# CurrentMonitor.net
KiCad netlist of a schematic drawn in EAGLE
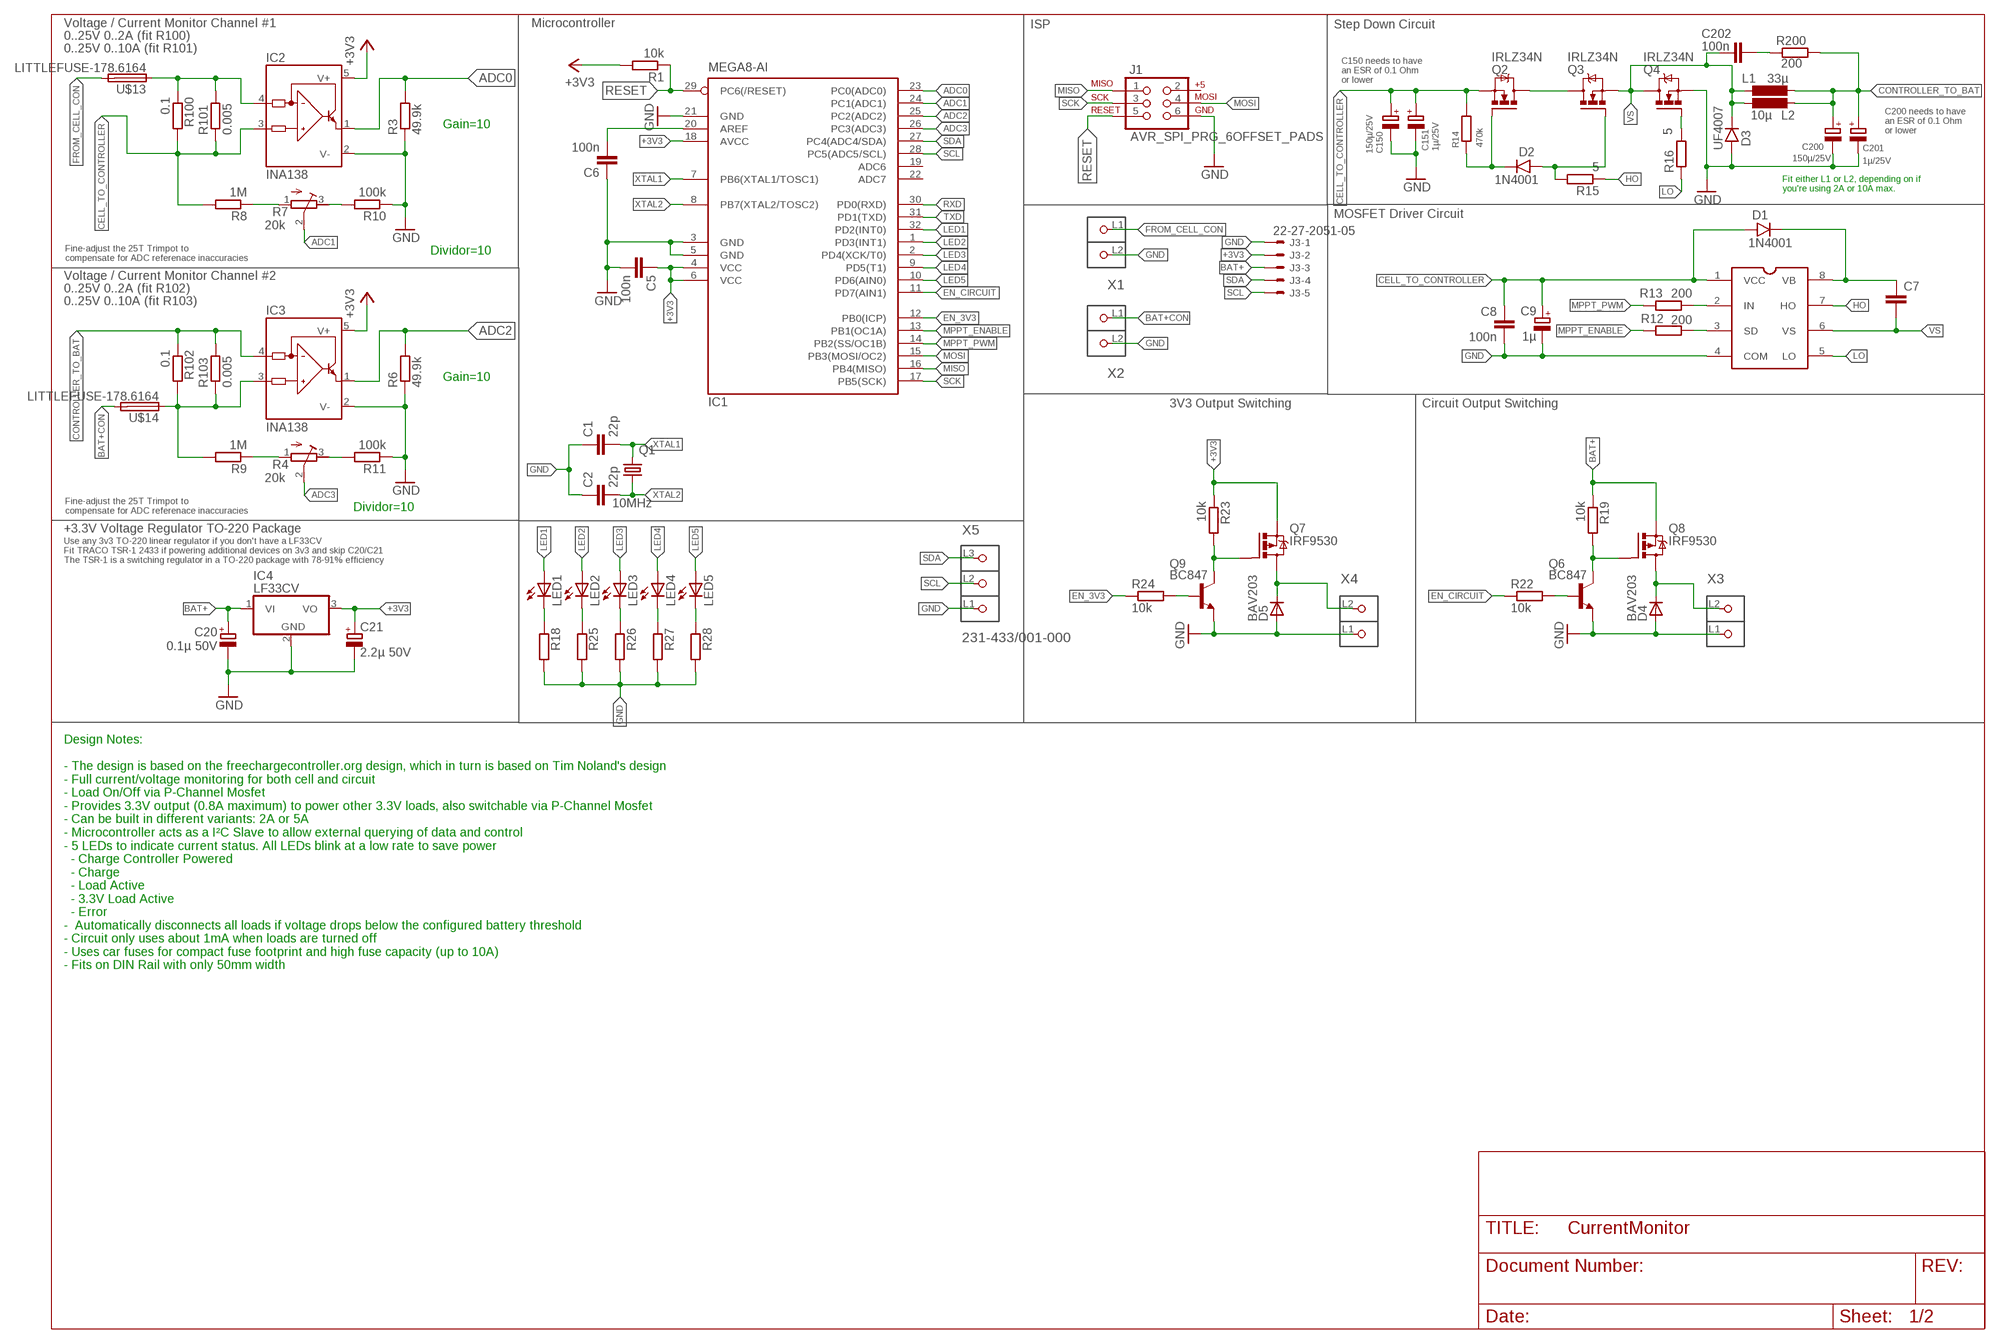
[diagram p0: schematic, sheet 1]
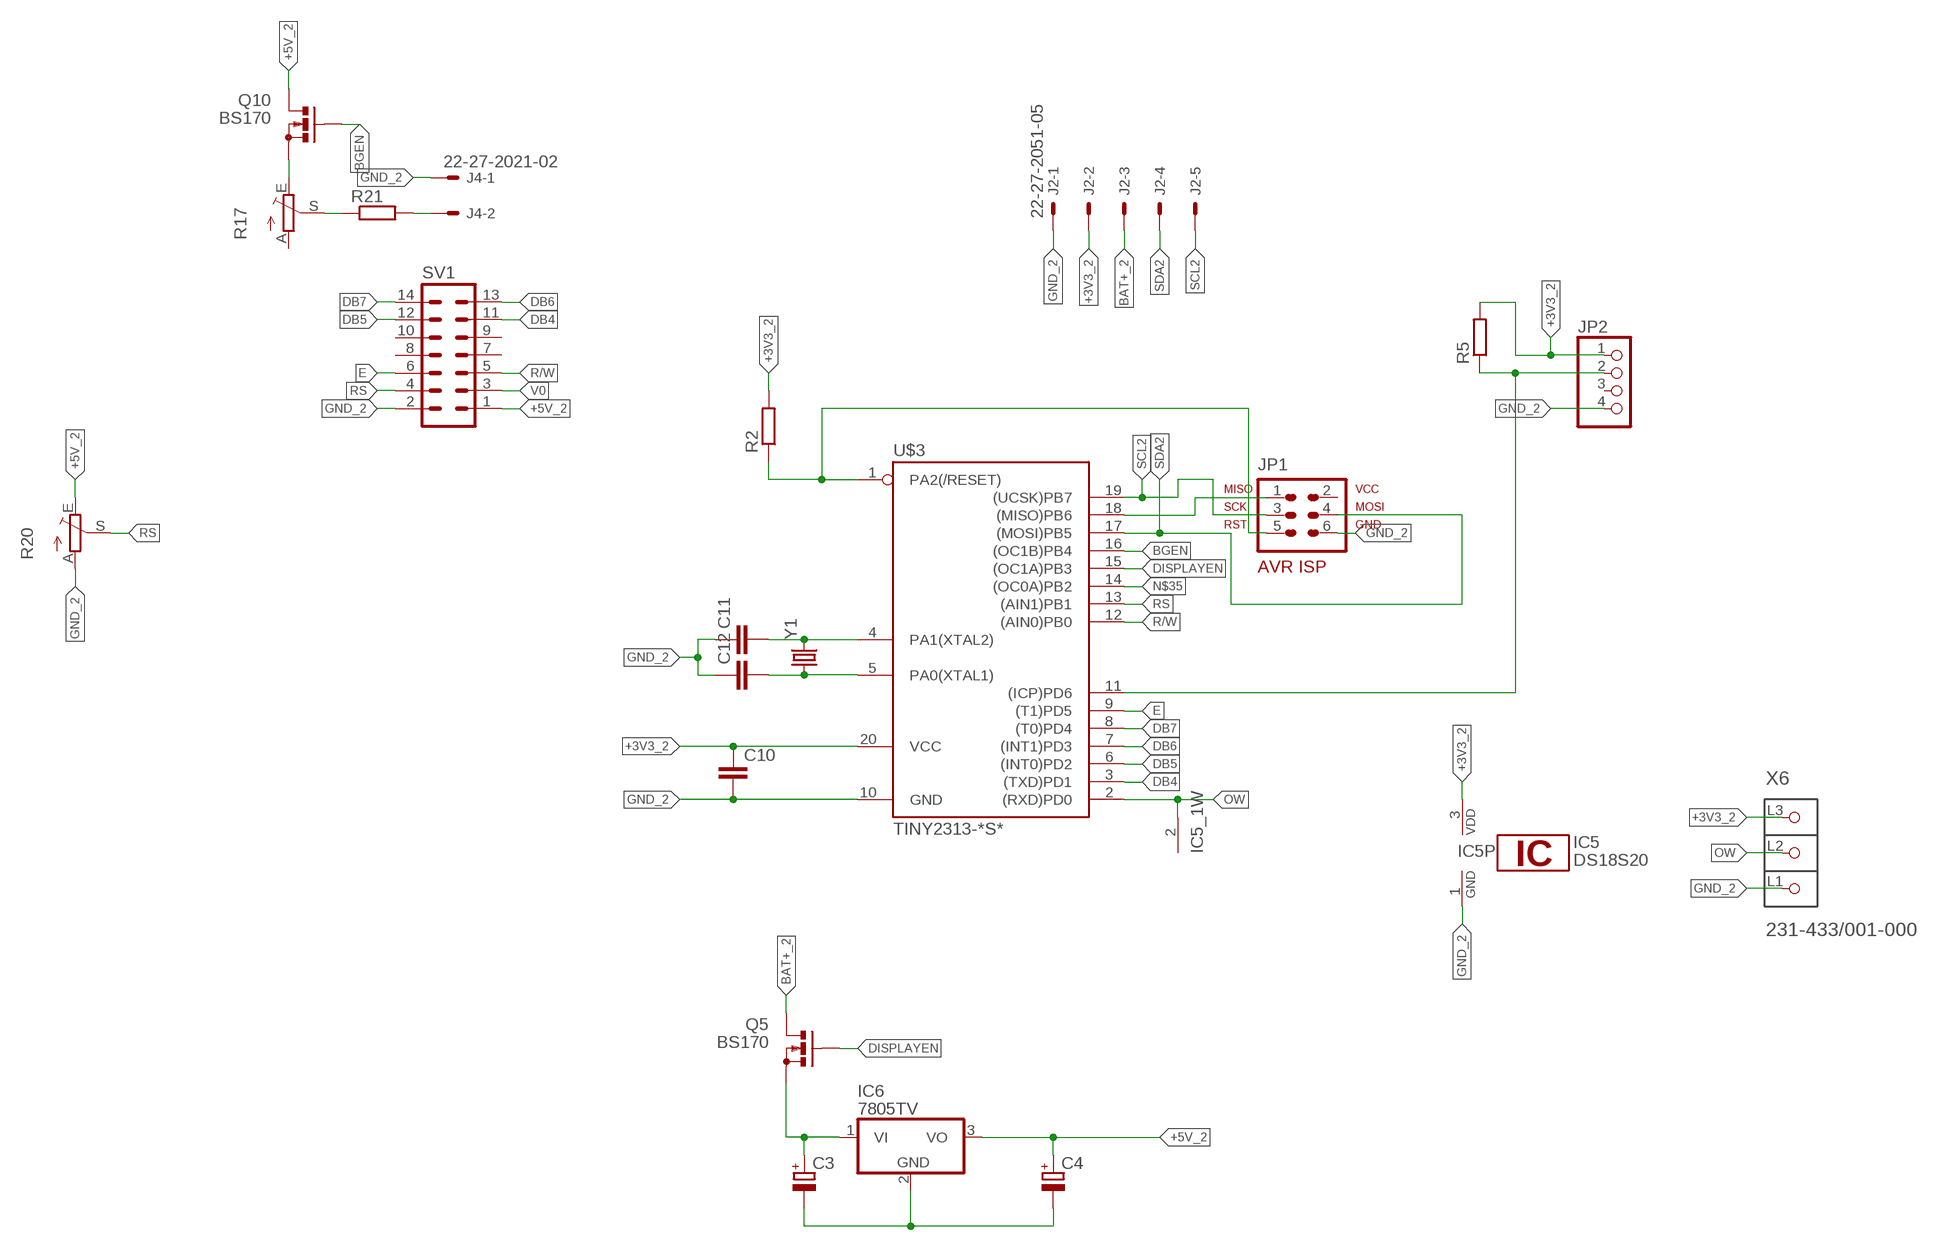
[diagram p1: schematic, sheet 2]

(export (version "E")
  (design (tool "Eeschema 10.0.6"))
  (components
    (comp (ref "C3")
      (value "CPOL-EUE3.5-8")
      (footprint "eagle-import:E3,5-8")
      (libsource (lib "eagle-import") (part "CPOL-EUE3.5-8"))
    )
    (comp (ref "C4")
      (value "CPOL-EUE3.5-8")
      (footprint "eagle-import:E3,5-8")
      (libsource (lib "eagle-import") (part "CPOL-EUE3.5-8"))
    )
    (comp (ref "C10")
      (value "C-EUC0805")
      (footprint "eagle-import:C0805")
      (libsource (lib "eagle-import") (part "C-EUC0805"))
    )
    (comp (ref "C11")
      (value "C-EUC0805")
      (footprint "eagle-import:C0805")
      (libsource (lib "eagle-import") (part "resistor_C-EUC0805"))
    )
    (comp (ref "C12")
      (value "C-EUC0805")
      (footprint "eagle-import:C0805")
      (libsource (lib "eagle-import") (part "resistor_C-EUC0805"))
    )
    (comp (ref "IC5")
      (value "DS18S20")
      (footprint "eagle-import:TO92-")
      (libsource (lib "eagle-import") (part "DS18S20"))
    )
    (comp (ref "IC6")
      (value "7805TV")
      (footprint "eagle-import:TO220V")
      (libsource (lib "eagle-import") (part "78TV05"))
    )
    (comp (ref "J2")
      (value "22-27-2051-05")
      (footprint "eagle-import:6410-05")
      (libsource (lib "eagle-import") (part "22-?-0527-2051"))
    )
    (comp (ref "J4")
      (value "22-27-2021-02")
      (footprint "eagle-import:6410-02")
      (libsource (lib "eagle-import") (part "22-?-0227-2021"))
    )
    (comp (ref "JP1")
      (value "AVR-ISP-6VERT")
      (footprint "eagle-import:AVR-ISP-6")
      (libsource (lib "eagle-import") (part "AVR-ISP-6VERT"))
    )
    (comp (ref "JP2")
      (value "PINHD-1X4")
      (footprint "eagle-import:1X04")
      (libsource (lib "eagle-import") (part "PINHD-1X4"))
    )
    (comp (ref "Q5")
      (value "BS170")
      (footprint "eagle-import:SOT54E")
      (libsource (lib "eagle-import") (part "BS170"))
    )
    (comp (ref "Q10")
      (value "BS170")
      (footprint "eagle-import:SOT54E")
      (libsource (lib "eagle-import") (part "BS170"))
    )
    (comp (ref "R2")
      (value "R-EU_R0805")
      (footprint "eagle-import:R0805")
      (libsource (lib "eagle-import") (part "R-EU_R0805"))
    )
    (comp (ref "R5")
      (value "R-EU_R0805")
      (footprint "eagle-import:R0805")
      (libsource (lib "eagle-import") (part "resistor_R-EU_R0805"))
    )
    (comp (ref "R17")
      (value "TRIM_EU-PT10")
      (footprint "eagle-import:PT-10")
      (libsource (lib "eagle-import") (part "TRIM_EU-PT10"))
    )
    (comp (ref "R20")
      (value "TRIM_EU-PT10")
      (footprint "eagle-import:PT-10")
      (libsource (lib "eagle-import") (part "TRIM_EU-PT10"))
    )
    (comp (ref "R21")
      (value "R-EU_R0805")
      (footprint "eagle-import:R0805")
      (libsource (lib "eagle-import") (part "R-EU_R0805"))
    )
    (comp (ref "SV1")
      (value "ML14")
      (footprint "eagle-import:ML14")
      (libsource (lib "eagle-import") (part "ML14"))
    )
    (comp (ref "U$3")
      (value "TINY2313-*S*")
      (footprint "eagle-import:SO20L$")
      (libsource (lib "eagle-import") (part "TINY2313-S"))
    )
    (comp (ref "X6")
      (value "231-433/001-000")
      (footprint "eagle-import:P-231-433_001-000")
      (libsource (lib "eagle-import") (part "231-433/001-000"))
    )
    (comp (ref "Y1")
      (value "CRYSTALHC49US")
      (footprint "eagle-import:HC49US")
      (libsource (lib "eagle-import") (part "CRYSTALHC49US"))
    )
    (comp (ref "C1")
      (value "22p")
      (footprint "eagle-import:C1206")
      (libsource (lib "eagle-import") (part "C-EUC1206"))
    )
    (comp (ref "C2")
      (value "22p")
      (footprint "eagle-import:C1206")
      (libsource (lib "eagle-import") (part "C-EUC1206"))
    )
    (comp (ref "C5")
      (value "100n")
      (footprint "eagle-import:C0805")
      (libsource (lib "eagle-import") (part "resistor_C-EUC0805"))
    )
    (comp (ref "C6")
      (value "100n")
      (footprint "eagle-import:C0805")
      (libsource (lib "eagle-import") (part "resistor_C-EUC0805"))
    )
    (comp (ref "C7")
      (value "C-EUC0805")
      (footprint "eagle-import:C0805")
      (libsource (lib "eagle-import") (part "resistor_C-EUC0805"))
    )
    (comp (ref "C8")
      (value "100n")
      (footprint "eagle-import:C0805")
      (libsource (lib "eagle-import") (part "resistor_C-EUC0805"))
    )
    (comp (ref "C9")
      (value "1µ")
      (footprint "eagle-import:PANASONIC_A")
      (libsource (lib "eagle-import") (part "CPOL-EUA"))
    )
    (comp (ref "C20")
      (value "0.1µ 50V")
      (footprint "eagle-import:PANASONIC_A")
      (libsource (lib "eagle-import") (part "CPOL-EUA"))
    )
    (comp (ref "C21")
      (value "2.2µ 50V")
      (footprint "eagle-import:PANASONIC_B")
      (libsource (lib "eagle-import") (part "CPOL-EUB"))
    )
    (comp (ref "C150")
      (value "150µ/25V")
      (footprint "eagle-import:PANASONIC_F")
      (libsource (lib "eagle-import") (part "CPOL-EUF"))
    )
    (comp (ref "C151")
      (value "1µ/25V")
      (footprint "eagle-import:PANASONIC_B")
      (libsource (lib "eagle-import") (part "CPOL-EUB"))
    )
    (comp (ref "C200")
      (value "150µ/25V")
      (footprint "eagle-import:PANASONIC_F")
      (libsource (lib "eagle-import") (part "CPOL-EUF"))
    )
    (comp (ref "C201")
      (value "1µ/25V")
      (footprint "eagle-import:PANASONIC_B")
      (libsource (lib "eagle-import") (part "CPOL-EUB"))
    )
    (comp (ref "C202")
      (value "100n")
      (footprint "eagle-import:C0805")
      (libsource (lib "eagle-import") (part "resistor_C-EUC0805"))
    )
    (comp (ref "D1")
      (value "1N4001")
      (footprint "eagle-import:DO41-3")
      (libsource (lib "eagle-import") (part "DO41.3"))
    )
    (comp (ref "D2")
      (value "1N4001")
      (footprint "eagle-import:DO41-3")
      (libsource (lib "eagle-import") (part "DO41.3"))
    )
    (comp (ref "D3")
      (value "UF4007")
      (footprint "eagle-import:DO41-3")
      (libsource (lib "eagle-import") (part "DO41.3"))
    )
    (comp (ref "D4")
      (value "BAV203")
      (footprint "eagle-import:SOD80")
      (libsource (lib "eagle-import") (part "D-SOD-80"))
    )
    (comp (ref "D5")
      (value "BAV203")
      (footprint "eagle-import:SOD80")
      (libsource (lib "eagle-import") (part "D-SOD-80"))
    )
    (comp (ref "IC1")
      (value "MEGA8-AI")
      (footprint "eagle-import:TQFP32-08")
      (fields (field (name "MPN") "ATMEGA8-16AU"))
      (libsource (lib "eagle-import") (part "MEGA8-AI"))
    )
    (comp (ref "IC2")
      (value "INA138")
      (footprint "eagle-import:SOT23-5")
      (fields (field (name "MF") "TEXAS INSTRUMENTS") (field (name "MPN") "INA138NA/250"))
      (libsource (lib "eagle-import") (part "INA138"))
    )
    (comp (ref "IC3")
      (value "INA138")
      (footprint "eagle-import:SOT23-5")
      (fields (field (name "MF") "TEXAS INSTRUMENTS") (field (name "MPN") "INA138NA/250"))
      (libsource (lib "eagle-import") (part "INA138"))
    )
    (comp (ref "IC4")
      (value "LF33CV")
      (footprint "eagle-import:TO220V")
      (libsource (lib "eagle-import") (part "78TV05"))
    )
    (comp (ref "J1")
      (value "AVR_SPI_PRG_6OFFSET_PADS")
      (footprint "eagle-import:2X3_OFFSET")
      (libsource (lib "eagle-import") (part "AVR_SPI_PRG_6OFFSET_PADS"))
    )
    (comp (ref "J3")
      (value "22-27-2051-05")
      (footprint "eagle-import:6410-05")
      (libsource (lib "eagle-import") (part "22-?-0527-2051"))
    )
    (comp (ref "L1")
      (value "33µ")
      (footprint "eagle-import:PISM")
      (libsource (lib "eagle-import") (part "L-EUPISM"))
    )
    (comp (ref "L2")
      (value "10µ")
      (footprint "eagle-import:PISR")
      (libsource (lib "eagle-import") (part "L-EUPISR"))
    )
    (comp (ref "LED1")
      (value "LEDCHIPLED_1206")
      (footprint "eagle-import:CHIPLED_1206")
      (libsource (lib "eagle-import") (part "LEDCHIPLED_1206"))
    )
    (comp (ref "LED2")
      (value "LEDCHIPLED_1206")
      (footprint "eagle-import:CHIPLED_1206")
      (libsource (lib "eagle-import") (part "LEDCHIPLED_1206"))
    )
    (comp (ref "LED3")
      (value "LEDCHIPLED_1206")
      (footprint "eagle-import:CHIPLED_1206")
      (libsource (lib "eagle-import") (part "LEDCHIPLED_1206"))
    )
    (comp (ref "LED4")
      (value "LEDCHIPLED_1206")
      (footprint "eagle-import:CHIPLED_1206")
      (libsource (lib "eagle-import") (part "LEDCHIPLED_1206"))
    )
    (comp (ref "LED5")
      (value "LEDCHIPLED_1206")
      (footprint "eagle-import:CHIPLED_1206")
      (libsource (lib "eagle-import") (part "LEDCHIPLED_1206"))
    )
    (comp (ref "Q1")
      (value "10MHz")
      (footprint "eagle-import:CTS406")
      (libsource (lib "eagle-import") (part "CRYSTALCTS406"))
    )
    (comp (ref "Q2")
      (value "IRLZ34N")
      (footprint "eagle-import:TO220BV")
      (libsource (lib "eagle-import") (part "IRF520"))
    )
    (comp (ref "Q3")
      (value "IRLZ34N")
      (footprint "eagle-import:TO220BV")
      (libsource (lib "eagle-import") (part "IRF520"))
    )
    (comp (ref "Q4")
      (value "IRLZ34N")
      (footprint "eagle-import:TO220BV")
      (libsource (lib "eagle-import") (part "IRF520"))
    )
    (comp (ref "Q6")
      (value "BC847")
      (footprint "eagle-import:SOT23")
      (libsource (lib "eagle-import") (part "BC847SMDALT1"))
    )
    (comp (ref "Q7")
      (value "IRF9530")
      (footprint "eagle-import:TO220BV")
      (libsource (lib "eagle-import") (part "IRF9530"))
    )
    (comp (ref "Q8")
      (value "IRF9530")
      (footprint "eagle-import:TO220BV")
      (libsource (lib "eagle-import") (part "IRF9530"))
    )
    (comp (ref "Q9")
      (value "BC847")
      (footprint "eagle-import:SOT23")
      (libsource (lib "eagle-import") (part "BC847SMDALT1"))
    )
    (comp (ref "R1")
      (value "10k")
      (footprint "eagle-import:R0805")
      (libsource (lib "eagle-import") (part "R-EU_R0805"))
    )
    (comp (ref "R3")
      (value "49.9k")
      (footprint "eagle-import:R0805")
      (libsource (lib "eagle-import") (part "R-EU_R0805"))
    )
    (comp (ref "R4")
      (value "20k")
      (footprint "eagle-import:RTRIM64W")
      (libsource (lib "eagle-import") (part "R-TRIMM64W"))
    )
    (comp (ref "R6")
      (value "49.9k")
      (footprint "eagle-import:R0805")
      (libsource (lib "eagle-import") (part "R-EU_R0805"))
    )
    (comp (ref "R7")
      (value "20k")
      (footprint "eagle-import:RTRIM64W")
      (libsource (lib "eagle-import") (part "R-TRIMM64W"))
    )
    (comp (ref "R8")
      (value "1M")
      (footprint "eagle-import:R0805")
      (libsource (lib "eagle-import") (part "R-EU_R0805"))
    )
    (comp (ref "R9")
      (value "1M")
      (footprint "eagle-import:R0805")
      (libsource (lib "eagle-import") (part "R-EU_R0805"))
    )
    (comp (ref "R10")
      (value "100k")
      (footprint "eagle-import:R0805")
      (libsource (lib "eagle-import") (part "R-EU_R0805"))
    )
    (comp (ref "R11")
      (value "100k")
      (footprint "eagle-import:R0805")
      (libsource (lib "eagle-import") (part "R-EU_R0805"))
    )
    (comp (ref "R12")
      (value "200")
      (footprint "eagle-import:R0805")
      (libsource (lib "eagle-import") (part "R-EU_R0805"))
    )
    (comp (ref "R13")
      (value "200")
      (footprint "eagle-import:R0805")
      (libsource (lib "eagle-import") (part "R-EU_R0805"))
    )
    (comp (ref "R14")
      (value "470k")
      (footprint "eagle-import:R0805")
      (libsource (lib "eagle-import") (part "R-EU_R0805"))
    )
    (comp (ref "R15")
      (value "5")
      (footprint "eagle-import:R0805")
      (libsource (lib "eagle-import") (part "resistor_R-EU_R0805"))
    )
    (comp (ref "R16")
      (value "5")
      (footprint "eagle-import:R0805")
      (libsource (lib "eagle-import") (part "resistor_R-EU_R0805"))
    )
    (comp (ref "R18")
      (value "R-EU_R0805")
      (footprint "eagle-import:R0805")
      (libsource (lib "eagle-import") (part "R-EU_R0805"))
    )
    (comp (ref "R19")
      (value "10k")
      (footprint "eagle-import:R0805")
      (libsource (lib "eagle-import") (part "R-EU_R0805"))
    )
    (comp (ref "R22")
      (value "10k")
      (footprint "eagle-import:R0805")
      (libsource (lib "eagle-import") (part "resistor_R-EU_R0805"))
    )
    (comp (ref "R23")
      (value "10k")
      (footprint "eagle-import:R0805")
      (libsource (lib "eagle-import") (part "R-EU_R0805"))
    )
    (comp (ref "R24")
      (value "10k")
      (footprint "eagle-import:R0805")
      (libsource (lib "eagle-import") (part "resistor_R-EU_R0805"))
    )
    (comp (ref "R25")
      (value "R-EU_R0805")
      (footprint "eagle-import:R0805")
      (libsource (lib "eagle-import") (part "R-EU_R0805"))
    )
    (comp (ref "R26")
      (value "R-EU_R0805")
      (footprint "eagle-import:R0805")
      (libsource (lib "eagle-import") (part "R-EU_R0805"))
    )
    (comp (ref "R27")
      (value "R-EU_R0805")
      (footprint "eagle-import:R0805")
      (libsource (lib "eagle-import") (part "R-EU_R0805"))
    )
    (comp (ref "R28")
      (value "R-EU_R0805")
      (footprint "eagle-import:R0805")
      (libsource (lib "eagle-import") (part "R-EU_R0805"))
    )
    (comp (ref "R100")
      (value "0.1")
      (footprint "eagle-import:R1206")
      (libsource (lib "eagle-import") (part "resistor_R-EU_R1206"))
    )
    (comp (ref "R101")
      (value "0.005")
      (footprint "eagle-import:R2512")
      (libsource (lib "eagle-import") (part "resistor_R-EU_R2512"))
    )
    (comp (ref "R102")
      (value "0.1")
      (footprint "eagle-import:R1206")
      (libsource (lib "eagle-import") (part "resistor_R-EU_R1206"))
    )
    (comp (ref "R103")
      (value "0.005")
      (footprint "eagle-import:R2512")
      (libsource (lib "eagle-import") (part "resistor_R-EU_R2512"))
    )
    (comp (ref "R200")
      (value "200")
      (footprint "eagle-import:R0805")
      (libsource (lib "eagle-import") (part "R-EU_R0805"))
    )
    (comp (ref "U$1")
      (value "IR2104S")
      (footprint "eagle-import:IR2104S")
      (libsource (lib "eagle-import") (part "IR2104S"))
    )
    (comp (ref "U$13")
      (value "LITTLEFUSE-178.6164")
      (footprint "eagle-import:LITTLEFUSE-178-6164")
      (libsource (lib "eagle-import") (part "LITTLEFUSE-178.6164"))
    )
    (comp (ref "U$14")
      (value "LITTLEFUSE-178.6164")
      (footprint "eagle-import:LITTLEFUSE-178-6164")
      (libsource (lib "eagle-import") (part "LITTLEFUSE-178.6164"))
    )
    (comp (ref "X1")
      (value "231-432/001-000")
      (footprint "eagle-import:P-231-432_001-000")
      (libsource (lib "eagle-import") (part "231-432/001-000"))
    )
    (comp (ref "X2")
      (value "231-432/001-000")
      (footprint "eagle-import:P-231-432_001-000")
      (libsource (lib "eagle-import") (part "231-432/001-000"))
    )
    (comp (ref "X3")
      (value "231-432/001-000")
      (footprint "eagle-import:P-231-432_001-000")
      (libsource (lib "eagle-import") (part "231-432/001-000"))
    )
    (comp (ref "X4")
      (value "231-432/001-000")
      (footprint "eagle-import:P-231-432_001-000")
      (libsource (lib "eagle-import") (part "231-432/001-000"))
    )
    (comp (ref "X5")
      (value "231-433/001-000")
      (footprint "eagle-import:P-231-433_001-000")
      (libsource (lib "eagle-import") (part "231-433/001-000"))
    )
  )
  (nets
    (net (code "1") (name "+3V3") (class "Default")
      (node (ref "C21") (pin "+") (pinfunction "+_+") (pintype "passive"))
      (node (ref "C5") (pin "1") (pinfunction "1_1") (pintype "passive"))
      (node (ref "IC1") (pin "18") (pinfunction "AVCC_18") (pintype "power_in"))
      (node (ref "IC1") (pin "4") (pinfunction "VCC_4") (pintype "power_in"))
      (node (ref "IC1") (pin "6") (pinfunction "VCC_6") (pintype "power_in"))
      (node (ref "IC2") (pin "5") (pinfunction "V+_5") (pintype "power_in"))
      (node (ref "IC3") (pin "5") (pinfunction "V+_5") (pintype "power_in"))
      (node (ref "IC4") (pin "3") (pinfunction "VO_3") (pintype "passive"))
      (node (ref "J3") (pin "2") (pinfunction "S_2") (pintype "passive"))
      (node (ref "Q7") (pin "S") (pinfunction "S_S") (pintype "passive"))
      (node (ref "R1") (pin "2") (pinfunction "2_2") (pintype "passive"))
      (node (ref "R23") (pin "1") (pinfunction "1_1") (pintype "passive"))
    )
    (net (code "2") (name "+3V3_2") (class "Default")
      (node (ref "C10") (pin "1") (pinfunction "1_1") (pintype "passive"))
      (node (ref "IC5") (pin "3") (pinfunction "VDD_3") (pintype "power_in"))
      (node (ref "J2") (pin "2") (pinfunction "S_2") (pintype "passive"))
      (node (ref "JP2") (pin "1") (pinfunction "1_1") (pintype "passive"))
      (node (ref "R2") (pin "2") (pinfunction "2_2") (pintype "passive"))
      (node (ref "R5") (pin "2") (pinfunction "2_2") (pintype "passive"))
      (node (ref "U$3") (pin "20") (pinfunction "VCC_20") (pintype "power_in"))
      (node (ref "X6") (pin "L3") (pinfunction "P3_L3") (pintype "bidirectional"))
    )
    (net (code "3") (name "+5V_2") (class "Default")
      (node (ref "C4") (pin "+") (pinfunction "+_+") (pintype "passive"))
      (node (ref "IC6") (pin "3") (pinfunction "VO_3") (pintype "passive"))
      (node (ref "Q10") (pin "D") (pinfunction "D_D") (pintype "passive"))
      (node (ref "R20") (pin "E") (pinfunction "E_E") (pintype "passive"))
      (node (ref "SV1") (pin "1") (pinfunction "1_1") (pintype "passive"))
    )
    (net (code "4") (name "ADC0") (class "Default")
      (node (ref "IC1") (pin "23") (pinfunction "PC0(ADC0)_23") (pintype "bidirectional"))
      (node (ref "IC2") (pin "1") (pinfunction "OUT_1") (pintype "output"))
      (node (ref "R3") (pin "2") (pinfunction "2_2") (pintype "passive"))
    )
    (net (code "5") (name "ADC1") (class "Default")
      (node (ref "IC1") (pin "24") (pinfunction "PC1(ADC1)_24") (pintype "bidirectional"))
      (node (ref "R7") (pin "2") (pinfunction "S_2") (pintype "passive"))
    )
    (net (code "6") (name "ADC2") (class "Default")
      (node (ref "IC1") (pin "25") (pinfunction "PC2(ADC2)_25") (pintype "bidirectional"))
      (node (ref "IC3") (pin "1") (pinfunction "OUT_1") (pintype "output"))
      (node (ref "R6") (pin "2") (pinfunction "2_2") (pintype "passive"))
    )
    (net (code "7") (name "ADC3") (class "Default")
      (node (ref "IC1") (pin "26") (pinfunction "PC3(ADC3)_26") (pintype "bidirectional"))
      (node (ref "R4") (pin "2") (pinfunction "S_2") (pintype "passive"))
    )
    (net (code "8") (name "BAT+") (class "Default")
      (node (ref "C20") (pin "+") (pinfunction "+_+") (pintype "passive"))
      (node (ref "IC3") (pin "3") (pinfunction "IN+_3") (pintype "input"))
      (node (ref "IC4") (pin "1") (pinfunction "VI_1") (pintype "input"))
      (node (ref "J3") (pin "3") (pinfunction "S_3") (pintype "passive"))
      (node (ref "Q8") (pin "S") (pinfunction "S_S") (pintype "passive"))
      (node (ref "R102") (pin "2") (pinfunction "2_2") (pintype "passive"))
      (node (ref "R103") (pin "1") (pinfunction "1_1") (pintype "passive"))
      (node (ref "R19") (pin "1") (pinfunction "1_1") (pintype "passive"))
      (node (ref "R9") (pin "2") (pinfunction "2_2") (pintype "passive"))
      (node (ref "U$14") (pin "P$1") (pinfunction "1_P$1") (pintype "passive"))
    )
    (net (code "9") (name "BAT+CON") (class "Default")
      (node (ref "U$14") (pin "P$2") (pinfunction "2_P$2") (pintype "passive"))
      (node (ref "X2") (pin "L1") (pinfunction "P1_L1") (pintype "bidirectional"))
    )
    (net (code "10") (name "BAT+_2") (class "Default")
      (node (ref "J2") (pin "3") (pinfunction "S_3") (pintype "passive"))
      (node (ref "Q5") (pin "D") (pinfunction "D_D") (pintype "passive"))
    )
    (net (code "11") (name "BGEN") (class "Default")
      (node (ref "Q10") (pin "G") (pinfunction "G_G") (pintype "passive"))
      (node (ref "U$3") (pin "16") (pinfunction "(OC1B)PB4_16") (pintype "bidirectional"))
    )
    (net (code "12") (name "CELL_TO_CONTROLLER") (class "Default")
      (node (ref "C150") (pin "+") (pinfunction "+_+") (pintype "passive"))
      (node (ref "C151") (pin "+") (pinfunction "+_+") (pintype "passive"))
      (node (ref "C8") (pin "1") (pinfunction "1_1") (pintype "passive"))
      (node (ref "C9") (pin "+") (pinfunction "+_+") (pintype "passive"))
      (node (ref "D1") (pin "A") (pinfunction "A_A") (pintype "passive"))
      (node (ref "IC2") (pin "3") (pinfunction "IN+_3") (pintype "input"))
      (node (ref "Q2") (pin "S") (pinfunction "S_S") (pintype "passive"))
      (node (ref "R100") (pin "2") (pinfunction "2_2") (pintype "passive"))
      (node (ref "R101") (pin "1") (pinfunction "1_1") (pintype "passive"))
      (node (ref "R14") (pin "2") (pinfunction "2_2") (pintype "passive"))
      (node (ref "R8") (pin "2") (pinfunction "2_2") (pintype "passive"))
      (node (ref "U$1") (pin "1") (pinfunction "VCC_1") (pintype "power_in"))
    )
    (net (code "13") (name "CONTROLLER_TO_BAT") (class "Default")
      (node (ref "C200") (pin "+") (pinfunction "+_+") (pintype "passive"))
      (node (ref "C201") (pin "+") (pinfunction "+_+") (pintype "passive"))
      (node (ref "IC3") (pin "4") (pinfunction "IN-_4") (pintype "input"))
      (node (ref "L1") (pin "2") (pinfunction "2_2") (pintype "passive"))
      (node (ref "L2") (pin "1") (pinfunction "1_1") (pintype "passive"))
      (node (ref "R102") (pin "1") (pinfunction "1_1") (pintype "passive"))
      (node (ref "R103") (pin "2") (pinfunction "2_2") (pintype "passive"))
      (node (ref "R200") (pin "2") (pinfunction "2_2") (pintype "passive"))
    )
    (net (code "14") (name "DB4") (class "Default")
      (node (ref "SV1") (pin "11") (pinfunction "11_11") (pintype "passive"))
      (node (ref "U$3") (pin "3") (pinfunction "(TXD)PD1_3") (pintype "bidirectional"))
    )
    (net (code "15") (name "DB5") (class "Default")
      (node (ref "SV1") (pin "12") (pinfunction "12_12") (pintype "passive"))
      (node (ref "U$3") (pin "6") (pinfunction "(INT0)PD2_6") (pintype "bidirectional"))
    )
    (net (code "16") (name "DB6") (class "Default")
      (node (ref "SV1") (pin "13") (pinfunction "13_13") (pintype "passive"))
      (node (ref "U$3") (pin "7") (pinfunction "(INT1)PD3_7") (pintype "bidirectional"))
    )
    (net (code "17") (name "DB7") (class "Default")
      (node (ref "SV1") (pin "14") (pinfunction "14_14") (pintype "passive"))
      (node (ref "U$3") (pin "8") (pinfunction "(T0)PD4_8") (pintype "bidirectional"))
    )
    (net (code "18") (name "DISPLAYEN") (class "Default")
      (node (ref "Q5") (pin "G") (pinfunction "G_G") (pintype "passive"))
      (node (ref "U$3") (pin "15") (pinfunction "(OC1A)PB3_15") (pintype "bidirectional"))
    )
    (net (code "19") (name "E") (class "Default")
      (node (ref "SV1") (pin "6") (pinfunction "6_6") (pintype "passive"))
      (node (ref "U$3") (pin "9") (pinfunction "(T1)PD5_9") (pintype "bidirectional"))
    )
    (net (code "20") (name "EN_3V3") (class "Default")
      (node (ref "IC1") (pin "12") (pinfunction "PB0(ICP)_12") (pintype "bidirectional"))
      (node (ref "R24") (pin "1") (pinfunction "1_1") (pintype "passive"))
    )
    (net (code "21") (name "EN_CIRCUIT") (class "Default")
      (node (ref "IC1") (pin "11") (pinfunction "PD7(AIN1)_11") (pintype "bidirectional"))
      (node (ref "R22") (pin "1") (pinfunction "1_1") (pintype "passive"))
    )
    (net (code "22") (name "FROM_CELL_CON") (class "Default")
      (node (ref "U$13") (pin "P$2") (pinfunction "2_P$2") (pintype "passive"))
      (node (ref "X1") (pin "L1") (pinfunction "P1_L1") (pintype "bidirectional"))
    )
    (net (code "23") (name "GND") (class "Default")
      (node (ref "C1") (pin "1") (pinfunction "1_1") (pintype "passive"))
      (node (ref "C150") (pin "-") (pinfunction "-_-") (pintype "passive"))
      (node (ref "C151") (pin "-") (pinfunction "-_-") (pintype "passive"))
      (node (ref "C2") (pin "1") (pinfunction "1_1") (pintype "passive"))
      (node (ref "C20") (pin "-") (pinfunction "-_-") (pintype "passive"))
      (node (ref "C200") (pin "-") (pinfunction "-_-") (pintype "passive"))
      (node (ref "C201") (pin "-") (pinfunction "-_-") (pintype "passive"))
      (node (ref "C21") (pin "-") (pinfunction "-_-") (pintype "passive"))
      (node (ref "C5") (pin "2") (pinfunction "2_2") (pintype "passive"))
      (node (ref "C6") (pin "1") (pinfunction "1_1") (pintype "passive"))
      (node (ref "C8") (pin "2") (pinfunction "2_2") (pintype "passive"))
      (node (ref "C9") (pin "-") (pinfunction "-_-") (pintype "passive"))
      (node (ref "D3") (pin "A") (pinfunction "A_A") (pintype "passive"))
      (node (ref "D4") (pin "2") (pinfunction "A_2") (pintype "passive"))
      (node (ref "D5") (pin "2") (pinfunction "A_2") (pintype "passive"))
      (node (ref "IC1") (pin "21") (pinfunction "GND_21") (pintype "power_in"))
      (node (ref "IC1") (pin "3") (pinfunction "GND_3") (pintype "power_in"))
      (node (ref "IC1") (pin "5") (pinfunction "GND_5") (pintype "power_in"))
      (node (ref "IC2") (pin "2") (pinfunction "V-_2") (pintype "power_in"))
      (node (ref "IC3") (pin "2") (pinfunction "V-_2") (pintype "power_in"))
      (node (ref "IC4") (pin "2") (pinfunction "GND_2") (pintype "passive"))
      (node (ref "J1") (pin "6") (pinfunction "6_6") (pintype "passive"))
      (node (ref "J3") (pin "1") (pinfunction "S_1") (pintype "passive"))
      (node (ref "Q4") (pin "S") (pinfunction "S_S") (pintype "passive"))
      (node (ref "Q6") (pin "2") (pinfunction "E_2") (pintype "passive"))
      (node (ref "Q9") (pin "2") (pinfunction "E_2") (pintype "passive"))
      (node (ref "R10") (pin "1") (pinfunction "1_1") (pintype "passive"))
      (node (ref "R11") (pin "1") (pinfunction "1_1") (pintype "passive"))
      (node (ref "R18") (pin "2") (pinfunction "2_2") (pintype "passive"))
      (node (ref "R25") (pin "2") (pinfunction "2_2") (pintype "passive"))
      (node (ref "R26") (pin "2") (pinfunction "2_2") (pintype "passive"))
      (node (ref "R27") (pin "2") (pinfunction "2_2") (pintype "passive"))
      (node (ref "R28") (pin "2") (pinfunction "2_2") (pintype "passive"))
      (node (ref "R3") (pin "1") (pinfunction "1_1") (pintype "passive"))
      (node (ref "R6") (pin "1") (pinfunction "1_1") (pintype "passive"))
      (node (ref "U$1") (pin "4") (pinfunction "COM_4") (pintype "bidirectional"))
      (node (ref "X1") (pin "L2") (pinfunction "P2_L2") (pintype "bidirectional"))
      (node (ref "X2") (pin "L2") (pinfunction "P2_L2") (pintype "bidirectional"))
      (node (ref "X3") (pin "L1") (pinfunction "P1_L1") (pintype "bidirectional"))
      (node (ref "X4") (pin "L1") (pinfunction "P1_L1") (pintype "bidirectional"))
      (node (ref "X5") (pin "L1") (pinfunction "P1_L1") (pintype "bidirectional"))
    )
    (net (code "24") (name "GND_2") (class "Default")
      (node (ref "C10") (pin "2") (pinfunction "2_2") (pintype "passive"))
      (node (ref "C11") (pin "1") (pinfunction "1_1") (pintype "passive"))
      (node (ref "C12") (pin "1") (pinfunction "1_1") (pintype "passive"))
      (node (ref "C3") (pin "-") (pinfunction "-_-") (pintype "passive"))
      (node (ref "C4") (pin "-") (pinfunction "-_-") (pintype "passive"))
      (node (ref "IC5") (pin "1") (pinfunction "GND_1") (pintype "power_in"))
      (node (ref "IC6") (pin "2") (pinfunction "GND_2") (pintype "passive"))
      (node (ref "J2") (pin "1") (pinfunction "S_1") (pintype "passive"))
      (node (ref "J4") (pin "1") (pinfunction "S_1") (pintype "passive"))
      (node (ref "JP1") (pin "6") (pinfunction "6_6") (pintype "passive"))
      (node (ref "JP2") (pin "4") (pinfunction "4_4") (pintype "passive"))
      (node (ref "R20") (pin "A") (pinfunction "A_A") (pintype "passive"))
      (node (ref "SV1") (pin "2") (pinfunction "2_2") (pintype "passive"))
      (node (ref "U$3") (pin "10") (pinfunction "GND_10") (pintype "power_in"))
      (node (ref "X6") (pin "L1") (pinfunction "P1_L1") (pintype "bidirectional"))
    )
    (net (code "25") (name "HO") (class "Default")
      (node (ref "R15") (pin "1") (pinfunction "1_1") (pintype "passive"))
      (node (ref "U$1") (pin "7") (pinfunction "HO_7") (pintype "bidirectional"))
    )
    (net (code "26") (name "LED1") (class "Default")
      (node (ref "IC1") (pin "32") (pinfunction "PD2(INT0)_32") (pintype "bidirectional"))
      (node (ref "LED1") (pin "A") (pinfunction "A_A") (pintype "passive"))
    )
    (net (code "27") (name "LED2") (class "Default")
      (node (ref "IC1") (pin "1") (pinfunction "PD3(INT1)_1") (pintype "bidirectional"))
      (node (ref "LED2") (pin "A") (pinfunction "A_A") (pintype "passive"))
    )
    (net (code "28") (name "LED3") (class "Default")
      (node (ref "IC1") (pin "2") (pinfunction "PD4(XCK/T0)_2") (pintype "bidirectional"))
      (node (ref "LED3") (pin "A") (pinfunction "A_A") (pintype "passive"))
    )
    (net (code "29") (name "LED4") (class "Default")
      (node (ref "IC1") (pin "9") (pinfunction "PD5(T1)_9") (pintype "bidirectional"))
      (node (ref "LED4") (pin "A") (pinfunction "A_A") (pintype "passive"))
    )
    (net (code "30") (name "LED5") (class "Default")
      (node (ref "IC1") (pin "10") (pinfunction "PD6(AIN0)_10") (pintype "bidirectional"))
      (node (ref "LED5") (pin "A") (pinfunction "A_A") (pintype "passive"))
    )
    (net (code "31") (name "LO") (class "Default")
      (node (ref "R16") (pin "1") (pinfunction "1_1") (pintype "passive"))
      (node (ref "U$1") (pin "5") (pinfunction "LO_5") (pintype "bidirectional"))
    )
    (net (code "32") (name "MISO") (class "Default")
      (node (ref "IC1") (pin "16") (pinfunction "PB4(MISO)_16") (pintype "bidirectional"))
      (node (ref "J1") (pin "1") (pinfunction "1_1") (pintype "passive"))
    )
    (net (code "33") (name "MOSI") (class "Default")
      (node (ref "IC1") (pin "15") (pinfunction "PB3(MOSI/OC2)_15") (pintype "bidirectional"))
      (node (ref "J1") (pin "4") (pinfunction "4_4") (pintype "passive"))
    )
    (net (code "34") (name "MPPT_ENABLE") (class "Default")
      (node (ref "IC1") (pin "13") (pinfunction "PB1(OC1A)_13") (pintype "bidirectional"))
      (node (ref "R12") (pin "1") (pinfunction "1_1") (pintype "passive"))
    )
    (net (code "35") (name "MPPT_PWM") (class "Default")
      (node (ref "IC1") (pin "14") (pinfunction "PB2(SS/OC1B)_14") (pintype "bidirectional"))
      (node (ref "R13") (pin "1") (pinfunction "1_1") (pintype "passive"))
    )
    (net (code "36") (name "N$35") (class "Default")
      (node (ref "U$3") (pin "14") (pinfunction "(OC0A)PB2_14") (pintype "bidirectional"))
    )
    (net (code "37") (name "Net-(C202-Pad1)") (class "Default")
      (node (ref "C202") (pin "1") (pinfunction "1_1") (pintype "passive"))
      (node (ref "R200") (pin "1") (pinfunction "1_1") (pintype "passive"))
    )
    (net (code "38") (name "Net-(D2-PadA)") (class "Default")
      (node (ref "D2") (pin "A") (pinfunction "A_A") (pintype "passive"))
      (node (ref "Q3") (pin "G") (pinfunction "G_G") (pintype "passive"))
      (node (ref "R15") (pin "2") (pinfunction "2_2") (pintype "passive"))
    )
    (net (code "39") (name "Net-(D2-PadC)") (class "Default")
      (node (ref "D2") (pin "C") (pinfunction "C_C") (pintype "passive"))
      (node (ref "Q2") (pin "G") (pinfunction "G_G") (pintype "passive"))
      (node (ref "R14") (pin "1") (pinfunction "1_1") (pintype "passive"))
    )
    (net (code "40") (name "Net-(D4-C)") (class "Default")
      (node (ref "D4") (pin "1") (pinfunction "C_1") (pintype "passive"))
      (node (ref "Q8") (pin "D") (pinfunction "D_D") (pintype "passive"))
      (node (ref "X3") (pin "L2") (pinfunction "P2_L2") (pintype "bidirectional"))
    )
    (net (code "41") (name "Net-(D5-C)") (class "Default")
      (node (ref "D5") (pin "1") (pinfunction "C_1") (pintype "passive"))
      (node (ref "Q7") (pin "D") (pinfunction "D_D") (pintype "passive"))
      (node (ref "X4") (pin "L2") (pinfunction "P2_L2") (pintype "bidirectional"))
    )
    (net (code "42") (name "Net-(IC1-AREF)") (class "Default")
      (node (ref "C6") (pin "2") (pinfunction "2_2") (pintype "passive"))
      (node (ref "IC1") (pin "20") (pinfunction "AREF_20") (pintype "passive"))
    )
    (net (code "43") (name "Net-(IC2-IN-)") (class "Default")
      (node (ref "IC2") (pin "4") (pinfunction "IN-_4") (pintype "input"))
      (node (ref "R100") (pin "1") (pinfunction "1_1") (pintype "passive"))
      (node (ref "R101") (pin "2") (pinfunction "2_2") (pintype "passive"))
      (node (ref "U$13") (pin "P$1") (pinfunction "1_P$1") (pintype "passive"))
    )
    (net (code "44") (name "Net-(IC6-VI)") (class "Default")
      (node (ref "C3") (pin "+") (pinfunction "+_+") (pintype "passive"))
      (node (ref "IC6") (pin "1") (pinfunction "VI_1") (pintype "input"))
      (node (ref "Q5") (pin "S") (pinfunction "S_S") (pintype "passive"))
    )
    (net (code "45") (name "Net-(J4B-S)") (class "Default")
      (node (ref "J4") (pin "2") (pinfunction "S_2") (pintype "passive"))
      (node (ref "R21") (pin "2") (pinfunction "2_2") (pintype "passive"))
    )
    (net (code "46") (name "Net-(LED1-PadC)") (class "Default")
      (node (ref "LED1") (pin "C") (pinfunction "C_C") (pintype "passive"))
      (node (ref "R18") (pin "1") (pinfunction "1_1") (pintype "passive"))
    )
    (net (code "47") (name "Net-(LED2-PadC)") (class "Default")
      (node (ref "LED2") (pin "C") (pinfunction "C_C") (pintype "passive"))
      (node (ref "R25") (pin "1") (pinfunction "1_1") (pintype "passive"))
    )
    (net (code "48") (name "Net-(LED3-PadC)") (class "Default")
      (node (ref "LED3") (pin "C") (pinfunction "C_C") (pintype "passive"))
      (node (ref "R26") (pin "1") (pinfunction "1_1") (pintype "passive"))
    )
    (net (code "49") (name "Net-(LED4-PadC)") (class "Default")
      (node (ref "LED4") (pin "C") (pinfunction "C_C") (pintype "passive"))
      (node (ref "R27") (pin "1") (pinfunction "1_1") (pintype "passive"))
    )
    (net (code "50") (name "Net-(LED5-PadC)") (class "Default")
      (node (ref "LED5") (pin "C") (pinfunction "C_C") (pintype "passive"))
      (node (ref "R28") (pin "1") (pinfunction "1_1") (pintype "passive"))
    )
    (net (code "51") (name "Net-(Q2-PadD)") (class "Default")
      (node (ref "Q2") (pin "D") (pinfunction "D_D") (pintype "passive"))
      (node (ref "Q3") (pin "D") (pinfunction "D_D") (pintype "passive"))
    )
    (net (code "52") (name "Net-(Q4-PadG)") (class "Default")
      (node (ref "Q4") (pin "G") (pinfunction "G_G") (pintype "passive"))
      (node (ref "R16") (pin "2") (pinfunction "2_2") (pintype "passive"))
    )
    (net (code "53") (name "Net-(Q6-B)") (class "Default")
      (node (ref "Q6") (pin "1") (pinfunction "B_1") (pintype "passive"))
      (node (ref "R22") (pin "2") (pinfunction "2_2") (pintype "passive"))
    )
    (net (code "54") (name "Net-(Q6-C)") (class "Default")
      (node (ref "Q6") (pin "3") (pinfunction "C_3") (pintype "passive"))
      (node (ref "Q8") (pin "G") (pinfunction "G_G") (pintype "passive"))
      (node (ref "R19") (pin "2") (pinfunction "2_2") (pintype "passive"))
    )
    (net (code "55") (name "Net-(Q9-B)") (class "Default")
      (node (ref "Q9") (pin "1") (pinfunction "B_1") (pintype "passive"))
      (node (ref "R24") (pin "2") (pinfunction "2_2") (pintype "passive"))
    )
    (net (code "56") (name "Net-(Q9-C)") (class "Default")
      (node (ref "Q7") (pin "G") (pinfunction "G_G") (pintype "passive"))
      (node (ref "Q9") (pin "3") (pinfunction "C_3") (pintype "passive"))
      (node (ref "R23") (pin "2") (pinfunction "2_2") (pintype "passive"))
    )
    (net (code "57") (name "Net-(Q10-PadS)") (class "Default")
      (node (ref "Q10") (pin "S") (pinfunction "S_S") (pintype "passive"))
      (node (ref "R17") (pin "E") (pinfunction "E_E") (pintype "passive"))
    )
    (net (code "58") (name "Net-(R4-A)") (class "Default")
      (node (ref "R4") (pin "1") (pinfunction "A_1") (pintype "passive"))
      (node (ref "R9") (pin "1") (pinfunction "1_1") (pintype "passive"))
    )
    (net (code "59") (name "Net-(R4-E)") (class "Default")
      (node (ref "R11") (pin "2") (pinfunction "2_2") (pintype "passive"))
      (node (ref "R4") (pin "3") (pinfunction "E_3") (pintype "passive"))
    )
    (net (code "60") (name "Net-(R7-A)") (class "Default")
      (node (ref "R7") (pin "1") (pinfunction "A_1") (pintype "passive"))
      (node (ref "R8") (pin "1") (pinfunction "1_1") (pintype "passive"))
    )
    (net (code "61") (name "Net-(R7-E)") (class "Default")
      (node (ref "R10") (pin "2") (pinfunction "2_2") (pintype "passive"))
      (node (ref "R7") (pin "3") (pinfunction "E_3") (pintype "passive"))
    )
    (net (code "62") (name "Net-(R17-PadS)") (class "Default")
      (node (ref "R17") (pin "S") (pinfunction "S_S") (pintype "passive"))
      (node (ref "R21") (pin "1") (pinfunction "1_1") (pintype "passive"))
    )
    (net (code "63") (name "Net-(U$1-IN)") (class "Default")
      (node (ref "R13") (pin "2") (pinfunction "2_2") (pintype "passive"))
      (node (ref "U$1") (pin "2") (pinfunction "IN_2") (pintype "bidirectional"))
    )
    (net (code "64") (name "Net-(U$1-SD)") (class "Default")
      (node (ref "R12") (pin "2") (pinfunction "2_2") (pintype "passive"))
      (node (ref "U$1") (pin "3") (pinfunction "SD_3") (pintype "bidirectional"))
    )
    (net (code "65") (name "Net-(U$1-VB)") (class "Default")
      (node (ref "C7") (pin "1") (pinfunction "1_1") (pintype "passive"))
      (node (ref "D1") (pin "C") (pinfunction "C_C") (pintype "passive"))
      (node (ref "U$1") (pin "8") (pinfunction "VB_8") (pintype "power_in"))
    )
    (net (code "66") (name "Net-(U$3-(ICP)PD6)") (class "Default")
      (node (ref "JP2") (pin "2") (pinfunction "2_2") (pintype "passive"))
      (node (ref "R5") (pin "1") (pinfunction "1_1") (pintype "passive"))
      (node (ref "U$3") (pin "11") (pinfunction "(ICP)PD6_11") (pintype "bidirectional"))
    )
    (net (code "67") (name "Net-(U$3-(MISO)PB6)") (class "Default")
      (node (ref "JP1") (pin "1") (pinfunction "1_1") (pintype "passive"))
      (node (ref "U$3") (pin "18") (pinfunction "(MISO)PB6_18") (pintype "bidirectional"))
    )
    (net (code "68") (name "Net-(U$3-PA0(XTAL1))") (class "Default")
      (node (ref "C12") (pin "2") (pinfunction "2_2") (pintype "passive"))
      (node (ref "U$3") (pin "5") (pinfunction "PA0(XTAL1)_5") (pintype "bidirectional"))
      (node (ref "Y1") (pin "1") (pinfunction "1_1") (pintype "passive"))
    )
    (net (code "69") (name "Net-(U$3-PA1(XTAL2))") (class "Default")
      (node (ref "C11") (pin "2") (pinfunction "2_2") (pintype "passive"))
      (node (ref "U$3") (pin "4") (pinfunction "PA1(XTAL2)_4") (pintype "bidirectional"))
      (node (ref "Y1") (pin "2") (pinfunction "2_2") (pintype "passive"))
    )
    (net (code "70") (name "Net-(U$3-PA2({slash}RESET))") (class "Default")
      (node (ref "JP1") (pin "5") (pinfunction "5_5") (pintype "passive"))
      (node (ref "R2") (pin "1") (pinfunction "1_1") (pintype "passive"))
      (node (ref "U$3") (pin "1") (pinfunction "PA2(/RESET)_1") (pintype "input"))
    )
    (net (code "71") (name "OW") (class "Default")
      (node (ref "IC5") (pin "2") (pinfunction "1W_2") (pintype "power_in"))
      (node (ref "U$3") (pin "2") (pinfunction "(RXD)PD0_2") (pintype "bidirectional"))
      (node (ref "X6") (pin "L2") (pinfunction "P2_L2") (pintype "bidirectional"))
    )
    (net (code "72") (name "RESET") (class "Default")
      (node (ref "IC1") (pin "29") (pinfunction "PC6(/RESET)_29") (pintype "bidirectional"))
      (node (ref "J1") (pin "5") (pinfunction "5_5") (pintype "passive"))
      (node (ref "R1") (pin "1") (pinfunction "1_1") (pintype "passive"))
    )
    (net (code "73") (name "RS") (class "Default")
      (node (ref "R20") (pin "S") (pinfunction "S_S") (pintype "passive"))
      (node (ref "SV1") (pin "4") (pinfunction "4_4") (pintype "passive"))
      (node (ref "U$3") (pin "13") (pinfunction "(AIN1)PB1_13") (pintype "bidirectional"))
    )
    (net (code "74") (name "RXD") (class "Default")
      (node (ref "IC1") (pin "30") (pinfunction "PD0(RXD)_30") (pintype "bidirectional"))
    )
    (net (code "75") (name "R{slash}W") (class "Default")
      (node (ref "SV1") (pin "5") (pinfunction "5_5") (pintype "passive"))
      (node (ref "U$3") (pin "12") (pinfunction "(AIN0)PB0_12") (pintype "bidirectional"))
    )
    (net (code "76") (name "SCK") (class "Default")
      (node (ref "IC1") (pin "17") (pinfunction "PB5(SCK)_17") (pintype "bidirectional"))
      (node (ref "J1") (pin "3") (pinfunction "3_3") (pintype "passive"))
    )
    (net (code "77") (name "SCL") (class "Default")
      (node (ref "IC1") (pin "28") (pinfunction "PC5(ADC5/SCL)_28") (pintype "bidirectional"))
      (node (ref "J3") (pin "5") (pinfunction "S_5") (pintype "passive"))
      (node (ref "X5") (pin "L2") (pinfunction "P2_L2") (pintype "bidirectional"))
    )
    (net (code "78") (name "SCL2") (class "Default")
      (node (ref "J2") (pin "5") (pinfunction "S_5") (pintype "passive"))
      (node (ref "JP1") (pin "3") (pinfunction "3_3") (pintype "passive"))
      (node (ref "U$3") (pin "19") (pinfunction "(UCSK)PB7_19") (pintype "bidirectional"))
    )
    (net (code "79") (name "SDA") (class "Default")
      (node (ref "IC1") (pin "27") (pinfunction "PC4(ADC4/SDA)_27") (pintype "bidirectional"))
      (node (ref "J3") (pin "4") (pinfunction "S_4") (pintype "passive"))
      (node (ref "X5") (pin "L3") (pinfunction "P3_L3") (pintype "bidirectional"))
    )
    (net (code "80") (name "SDA2") (class "Default")
      (node (ref "J2") (pin "4") (pinfunction "S_4") (pintype "passive"))
      (node (ref "JP1") (pin "4") (pinfunction "4_4") (pintype "passive"))
      (node (ref "U$3") (pin "17") (pinfunction "(MOSI)PB5_17") (pintype "bidirectional"))
    )
    (net (code "81") (name "TXD") (class "Default")
      (node (ref "IC1") (pin "31") (pinfunction "PD1(TXD)_31") (pintype "bidirectional"))
    )
    (net (code "82") (name "V0") (class "Default")
      (node (ref "SV1") (pin "3") (pinfunction "3_3") (pintype "passive"))
    )
    (net (code "83") (name "VS") (class "Default")
      (node (ref "C202") (pin "2") (pinfunction "2_2") (pintype "passive"))
      (node (ref "C7") (pin "2") (pinfunction "2_2") (pintype "passive"))
      (node (ref "D3") (pin "C") (pinfunction "C_C") (pintype "passive"))
      (node (ref "L1") (pin "1") (pinfunction "1_1") (pintype "passive"))
      (node (ref "L2") (pin "2") (pinfunction "2_2") (pintype "passive"))
      (node (ref "Q3") (pin "S") (pinfunction "S_S") (pintype "passive"))
      (node (ref "Q4") (pin "D") (pinfunction "D_D") (pintype "passive"))
      (node (ref "U$1") (pin "6") (pinfunction "VS_6") (pintype "power_in"))
    )
    (net (code "84") (name "XTAL1") (class "Default")
      (node (ref "C1") (pin "2") (pinfunction "2_2") (pintype "passive"))
      (node (ref "IC1") (pin "7") (pinfunction "PB6(XTAL1/TOSC1)_7") (pintype "bidirectional"))
      (node (ref "Q1") (pin "3") (pinfunction "2_3") (pintype "passive"))
    )
    (net (code "85") (name "XTAL2") (class "Default")
      (node (ref "C2") (pin "2") (pinfunction "2_2") (pintype "passive"))
      (node (ref "IC1") (pin "8") (pinfunction "PB7(XTAL2/TOSC2)_8") (pintype "bidirectional"))
      (node (ref "Q1") (pin "1") (pinfunction "1_1") (pintype "passive"))
    )
    (net (code "86") (name "unconnected-(IC1-ADC6-Pad19)") (class "Default")
      (node (ref "IC1") (pin "19") (pinfunction "ADC6_19") (pintype "bidirectional"))
    )
    (net (code "87") (name "unconnected-(IC1-ADC7-Pad22)") (class "Default")
      (node (ref "IC1") (pin "22") (pinfunction "ADC7_22") (pintype "bidirectional"))
    )
    (net (code "88") (name "unconnected-(J1-Pad2)") (class "Default")
      (node (ref "J1") (pin "2") (pinfunction "2_2") (pintype "passive"))
    )
    (net (code "89") (name "unconnected-(JP1-Pad2)") (class "Default")
      (node (ref "JP1") (pin "2") (pinfunction "2_2") (pintype "passive"))
    )
    (net (code "90") (name "unconnected-(JP2-Pad3)") (class "Default")
      (node (ref "JP2") (pin "3") (pinfunction "3_3") (pintype "passive"))
    )
    (net (code "91") (name "unconnected-(R17-PadA)") (class "Default")
      (node (ref "R17") (pin "A") (pinfunction "A_A") (pintype "passive"))
    )
    (net (code "92") (name "unconnected-(SV1-Pad7)") (class "Default")
      (node (ref "SV1") (pin "7") (pinfunction "7_7") (pintype "passive"))
    )
    (net (code "93") (name "unconnected-(SV1-Pad8)") (class "Default")
      (node (ref "SV1") (pin "8") (pinfunction "8_8") (pintype "passive"))
    )
    (net (code "94") (name "unconnected-(SV1-Pad9)") (class "Default")
      (node (ref "SV1") (pin "9") (pinfunction "9_9") (pintype "passive"))
    )
    (net (code "95") (name "unconnected-(SV1-Pad10)") (class "Default")
      (node (ref "SV1") (pin "10") (pinfunction "10_10") (pintype "passive"))
    )
  )
)
